# distance_sensor.net
KiCad netlist of a schematic drawn in EAGLE
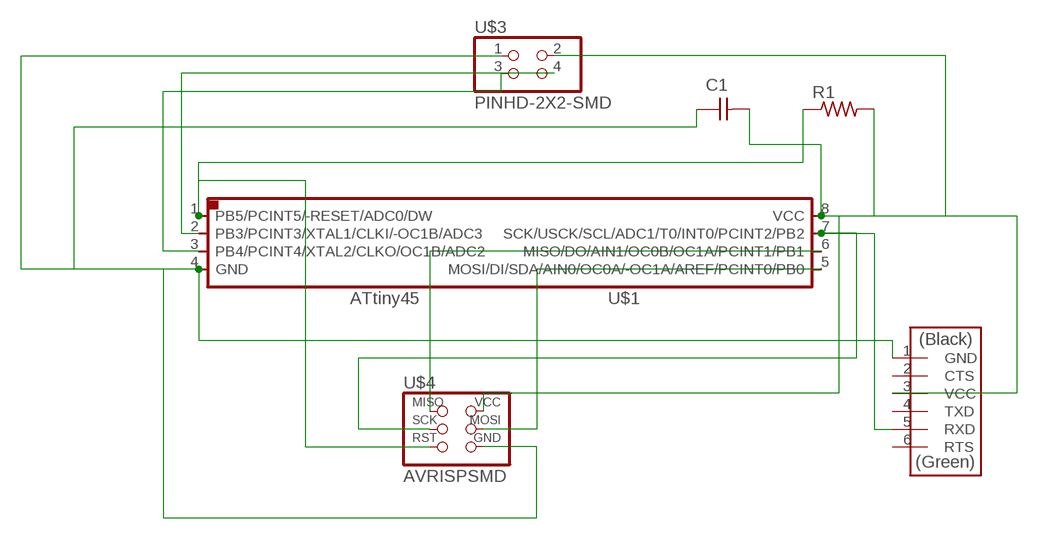
[diagram p0: schematic, sheet 1]

(export (version "E")
  (design (tool "Eeschema 10.0.6"))
  (components
    (comp (ref "C1")
      (value "CAP-UNPOLARIZEDFAB")
      (footprint "eagle-import:C1206FAB")
      (libsource (lib "eagle-import") (part "CAP-UNPOLARIZEDFAB"))
    )
    (comp (ref "R1")
      (value "RES-US1206FAB")
      (footprint "eagle-import:R1206FAB")
      (libsource (lib "eagle-import") (part "RES-US1206FAB"))
    )
    (comp (ref "U$1")
      (value "ATTINY45SI")
      (footprint "eagle-import:SOIC8")
      (libsource (lib "eagle-import") (part "ATTINY45SI"))
    )
    (comp (ref "U$2")
      (value "FTDI-SMD-HEADER")
      (footprint "eagle-import:1X06SMD")
      (libsource (lib "eagle-import") (part "FTDI-SMD-HEADER"))
    )
    (comp (ref "U$3")
      (value "PINHD-2X2-SMD")
      (footprint "eagle-import:2X02SMD")
      (libsource (lib "eagle-import") (part "PINHD-2X2-SMD"))
    )
    (comp (ref "U$4")
      (value "AVRISPSMD")
      (footprint "eagle-import:2X03SMD")
      (libsource (lib "eagle-import") (part "AVRISPSMD"))
    )
  )
  (nets
    (net (code "1") (name "Net-(U$1-GND)") (class "Default")
      (node (ref "C1") (pin "1") (pinfunction "1_1") (pintype "passive"))
      (node (ref "U$1") (pin "4") (pinfunction "GND_4") (pintype "bidirectional"))
      (node (ref "U$2") (pin "1") (pinfunction "GND_1") (pintype "bidirectional"))
      (node (ref "U$3") (pin "1") (pinfunction "1_1") (pintype "passive"))
      (node (ref "U$4") (pin "6") (pinfunction "GND_6") (pintype "passive"))
    )
    (net (code "2") (name "Net-(U$1-MISO{slash}DO{slash}AIN1{slash}OC0B{slash}OC1A{slash}PCINT1{slash}PB1)") (class "Default")
      (node (ref "U$1") (pin "6") (pinfunction "MISO/DO/AIN1/OC0B/OC1A/PCINT1/PB1_6") (pintype "bidirectional"))
      (node (ref "U$4") (pin "1") (pinfunction "MISO_1") (pintype "passive"))
    )
    (net (code "3") (name "Net-(U$1-MOSI{slash}DI{slash}SDA{slash}AIN0{slash}OC0A{slash}-OC1A{slash}AREF{slash}PCINT0{slash}PB0)") (class "Default")
      (node (ref "U$1") (pin "5") (pinfunction "MOSI/DI/SDA/AIN0/OC0A/-OC1A/AREF/PCINT0/PB0_5") (pintype "bidirectional"))
      (node (ref "U$4") (pin "4") (pinfunction "MOSI_4") (pintype "passive"))
    )
    (net (code "4") (name "Net-(U$1-PB3{slash}PCINT3{slash}XTAL1{slash}CLKI{slash}-OC1B{slash}ADC3)") (class "Default")
      (node (ref "U$1") (pin "2") (pinfunction "PB3/PCINT3/XTAL1/CLKI/-OC1B/ADC3_2") (pintype "bidirectional"))
      (node (ref "U$3") (pin "4") (pinfunction "4_4") (pintype "passive"))
    )
    (net (code "5") (name "Net-(U$1-PB4{slash}PCINT4{slash}XTAL2{slash}CLKO{slash}OC1B{slash}ADC2)") (class "Default")
      (node (ref "U$1") (pin "3") (pinfunction "PB4/PCINT4/XTAL2/CLKO/OC1B/ADC2_3") (pintype "bidirectional"))
      (node (ref "U$3") (pin "3") (pinfunction "3_3") (pintype "passive"))
    )
    (net (code "6") (name "Net-(U$1-PB5{slash}PCINT5{slash}-RESET{slash}ADC0{slash}DW)") (class "Default")
      (node (ref "R1") (pin "1") (pinfunction "1_1") (pintype "passive"))
      (node (ref "U$1") (pin "1") (pinfunction "PB5/PCINT5/-RESET/ADC0/DW_1") (pintype "bidirectional"))
      (node (ref "U$4") (pin "5") (pinfunction "RST_5") (pintype "passive"))
    )
    (net (code "7") (name "Net-(U$1-SCK{slash}USCK{slash}SCL{slash}ADC1{slash}T0{slash}INT0{slash}PCINT2{slash}PB2)") (class "Default")
      (node (ref "U$1") (pin "7") (pinfunction "SCK/USCK/SCL/ADC1/T0/INT0/PCINT2/PB2_7") (pintype "bidirectional"))
      (node (ref "U$2") (pin "5") (pinfunction "RXD_5") (pintype "bidirectional"))
      (node (ref "U$4") (pin "3") (pinfunction "SCK_3") (pintype "passive"))
    )
    (net (code "8") (name "Net-(U$1-VCC)") (class "Default")
      (node (ref "C1") (pin "2") (pinfunction "2_2") (pintype "passive"))
      (node (ref "R1") (pin "2") (pinfunction "2_2") (pintype "passive"))
      (node (ref "U$1") (pin "8") (pinfunction "VCC_8") (pintype "bidirectional"))
      (node (ref "U$2") (pin "3") (pinfunction "VCC_3") (pintype "bidirectional"))
      (node (ref "U$3") (pin "2") (pinfunction "2_2") (pintype "passive"))
      (node (ref "U$4") (pin "2") (pinfunction "VCC_2") (pintype "passive"))
    )
    (net (code "9") (name "unconnected-(U$2-CTS-Pad2)") (class "Default")
      (node (ref "U$2") (pin "2") (pinfunction "CTS_2") (pintype "bidirectional"))
    )
    (net (code "10") (name "unconnected-(U$2-RTS-Pad6)") (class "Default")
      (node (ref "U$2") (pin "6") (pinfunction "RTS_6") (pintype "bidirectional"))
    )
    (net (code "11") (name "unconnected-(U$2-TXD-Pad4)") (class "Default")
      (node (ref "U$2") (pin "4") (pinfunction "TXD_4") (pintype "bidirectional"))
    )
  )
)
